# OnOnfre_Lights.net
KiCad netlist of a schematic drawn in EAGLE
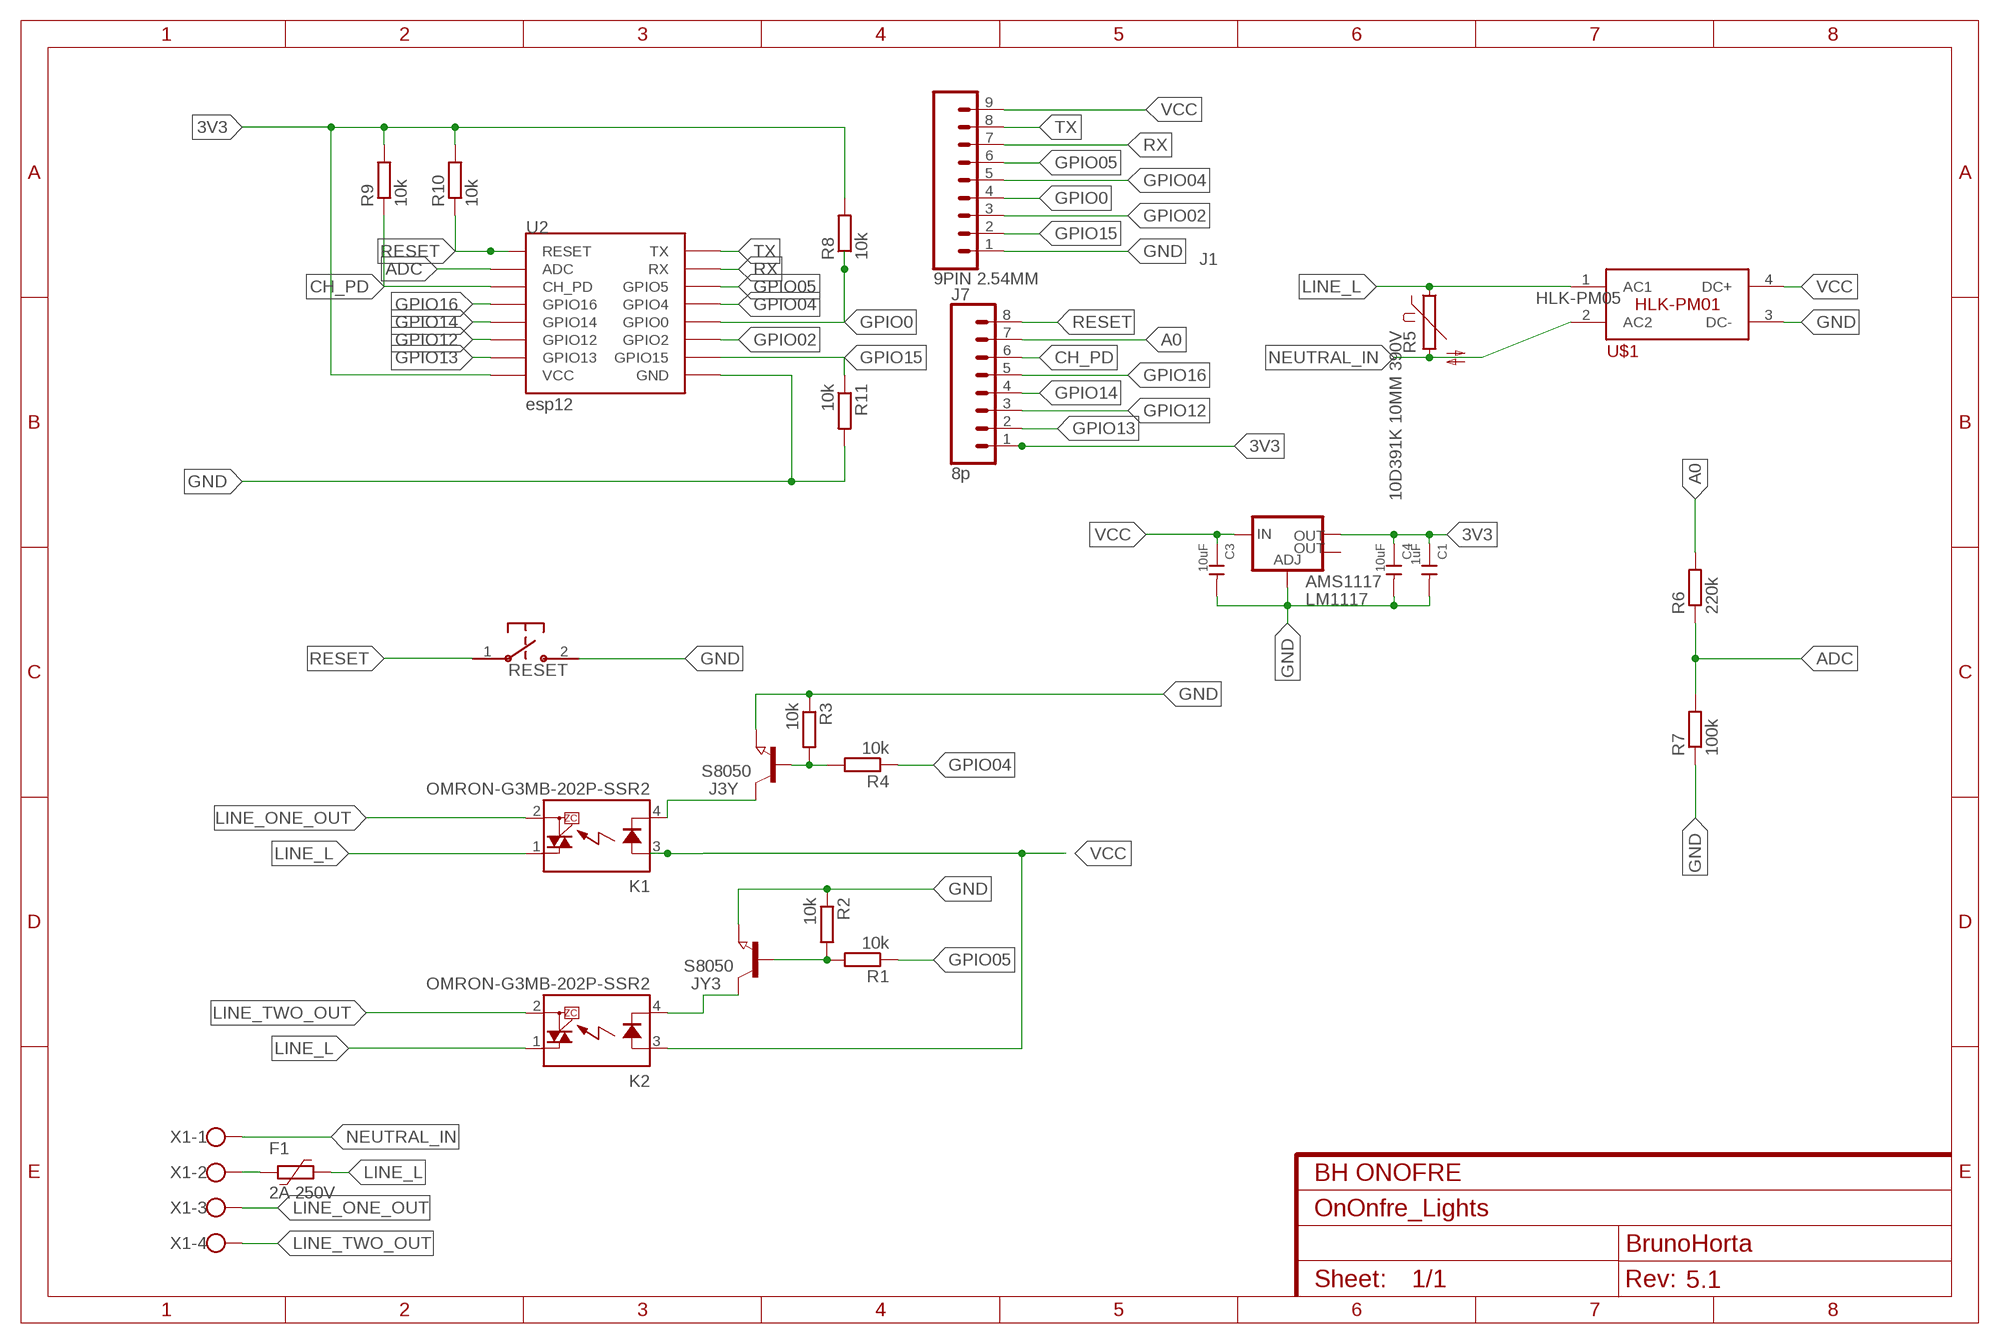
[diagram p0: schematic, sheet 1]

(export (version "E")
  (design (tool "Eeschema 10.0.6"))
  (components
    (comp (ref "AMS1117")
      (value "LM1117")
      (footprint "eagle-import:SOT223")
      (libsource (lib "eagle-import") (part "V_REG_LM1117SOT223"))
    )
    (comp (ref "C1")
      (value "1uF")
      (footprint "eagle-import:C1206")
      (fields (field (name "MPN") "CC1206KKX7RCBB102"))
      (libsource (lib "eagle-import") (part "CERAMIC-1NF-1KV-10%-X7R?(1206)"))
    )
    (comp (ref "C3")
      (value "10uF")
      (footprint "eagle-import:C1206")
      (fields (field (name "MPN") "CC1206KKX7RCBB102"))
      (libsource (lib "eagle-import") (part "CERAMIC-1NF-1KV-10%-X7R?(1206)"))
    )
    (comp (ref "C4")
      (value "10uF")
      (footprint "eagle-import:C1206")
      (fields (field (name "MPN") "CC1206KKX7RCBB102"))
      (libsource (lib "eagle-import") (part "CERAMIC-1NF-1KV-10%-X7R?(1206)"))
    )
    (comp (ref "F1")
      (value "2A 250V")
      (footprint "eagle-import:1812L")
      (fields (field (name "MF") "Littelfuse") (field (name "MPN") "1812L010"))
      (libsource (lib "eagle-import") (part "?1812L010"))
    )
    (comp (ref "J1")
      (value "9PIN 2.54MM")
      (footprint "eagle-import:1X09")
      (libsource (lib "eagle-import") (part "CONN_09"))
    )
    (comp (ref "J3Y")
      (value "S8050")
      (footprint "eagle-import:SOT23")
      (libsource (lib "eagle-import") (part "NPN-TRANSISTOR_SOT23"))
    )
    (comp (ref "J7")
      (value "8p")
      (footprint "eagle-import:1X08")
      (libsource (lib "eagle-import") (part "CONN_08{dblquote}"))
    )
    (comp (ref "JY3")
      (value "S8050")
      (footprint "eagle-import:SOT23")
      (libsource (lib "eagle-import") (part "NPN-TRANSISTOR_SOT23"))
    )
    (comp (ref "K1")
      (value "OMRON-G3MB-202P-SSR2")
      (footprint "eagle-import:OMRON-G3MB-202P-SSR")
      (fields (field (name "MPN") "S202S02F"))
      (libsource (lib "eagle-import") (part "OMRON-G3MB-202P-SSR2"))
    )
    (comp (ref "K2")
      (value "OMRON-G3MB-202P-SSR2")
      (footprint "eagle-import:OMRON-G3MB-202P-SSR")
      (fields (field (name "MPN") "S202S02F"))
      (libsource (lib "eagle-import") (part "OMRON-G3MB-202P-SSR2"))
    )
    (comp (ref "R1")
      (value "10k")
      (footprint "eagle-import:R0603")
      (libsource (lib "eagle-import") (part "R-EU_R0603"))
    )
    (comp (ref "R2")
      (value "10k")
      (footprint "eagle-import:R0603")
      (libsource (lib "eagle-import") (part "R-EU_R0603"))
    )
    (comp (ref "R3")
      (value "10k")
      (footprint "eagle-import:R0603")
      (libsource (lib "eagle-import") (part "R-EU_R0603"))
    )
    (comp (ref "R4")
      (value "10k")
      (footprint "eagle-import:R0603")
      (libsource (lib "eagle-import") (part "R-EU_R0603"))
    )
    (comp (ref "R5")
      (value "10D391K 10MM 390V")
      (footprint "eagle-import:S07K230")
      (libsource (lib "eagle-import") (part "S07K230"))
    )
    (comp (ref "R6")
      (value "220k")
      (footprint "eagle-import:R0603")
      (libsource (lib "eagle-import") (part "R-EU_R0603"))
    )
    (comp (ref "R7")
      (value "100k")
      (footprint "eagle-import:R0603")
      (libsource (lib "eagle-import") (part "R-EU_R0603"))
    )
    (comp (ref "R8")
      (value "10k")
      (footprint "eagle-import:R0603")
      (libsource (lib "eagle-import") (part "R-EU_R0603"))
    )
    (comp (ref "R9")
      (value "10k")
      (footprint "eagle-import:R0603")
      (libsource (lib "eagle-import") (part "R-EU_R0603"))
    )
    (comp (ref "R10")
      (value "10k")
      (footprint "eagle-import:R0603")
      (libsource (lib "eagle-import") (part "R-EU_R0603"))
    )
    (comp (ref "R11")
      (value "10k")
      (footprint "eagle-import:R0603")
      (libsource (lib "eagle-import") (part "R-EU_R0603"))
    )
    (comp (ref "RESET")
      (value "B3U-1000P-2P-SMD")
      (footprint "eagle-import:B3U-1000P")
      (fields (field (name "MANUFACTURER") "Omron") (field (name "MPN") "B3U-1000P"))
      (libsource (lib "eagle-import") (part "B3U-1000P"))
    )
    (comp (ref "U$1")
      (value "HLK-PM01")
      (footprint "eagle-import:HLK-PM01")
      (fields (field (name "MF") "Hi-link") (field (name "MP") "hlk-pm01"))
      (libsource (lib "eagle-import") (part "HLK-PM01"))
    )
    (comp (ref "U2")
      (value "esp12")
      (footprint "eagle-import:ESP12-SMD")
      (libsource (lib "eagle-import") (part "ESP12SMD"))
    )
    (comp (ref "X1")
      (value "W237-4")
      (footprint "eagle-import:W237-4")
      (libsource (lib "eagle-import") (part "W237-4"))
    )
  )
  (nets
    (net (code "1") (name "3V3") (class "Default")
      (node (ref "AMS1117") (pin "2") (pinfunction "OUT_2") (pintype "output"))
      (node (ref "C1") (pin "1") (pinfunction "1_1") (pintype "passive"))
      (node (ref "C4") (pin "1") (pinfunction "1_1") (pintype "passive"))
      (node (ref "J7") (pin "1") (pinfunction "1_1") (pintype "passive"))
      (node (ref "R10") (pin "2") (pinfunction "2_2") (pintype "passive"))
      (node (ref "R8") (pin "2") (pinfunction "2_2") (pintype "passive"))
      (node (ref "R9") (pin "2") (pinfunction "2_2") (pintype "passive"))
      (node (ref "U2") (pin "VCC") (pinfunction "VCC_VCC") (pintype "bidirectional"))
    )
    (net (code "2") (name "A0") (class "Default")
      (node (ref "J7") (pin "7") (pinfunction "7_7") (pintype "passive"))
      (node (ref "R6") (pin "2") (pinfunction "2_2") (pintype "passive"))
    )
    (net (code "3") (name "ADC") (class "Default")
      (node (ref "R6") (pin "1") (pinfunction "1_1") (pintype "passive"))
      (node (ref "R7") (pin "2") (pinfunction "2_2") (pintype "passive"))
      (node (ref "U2") (pin "ADC") (pinfunction "ADC_ADC") (pintype "bidirectional"))
    )
    (net (code "4") (name "CH_PD") (class "Default")
      (node (ref "J7") (pin "6") (pinfunction "6_6") (pintype "passive"))
      (node (ref "R9") (pin "1") (pinfunction "1_1") (pintype "passive"))
      (node (ref "U2") (pin "CH_PD") (pinfunction "CH_PD_CH_PD") (pintype "bidirectional"))
    )
    (net (code "5") (name "GND") (class "Default")
      (node (ref "AMS1117") (pin "1") (pinfunction "ADJ_1") (pintype "input"))
      (node (ref "C1") (pin "2") (pinfunction "2_2") (pintype "passive"))
      (node (ref "C3") (pin "2") (pinfunction "2_2") (pintype "passive"))
      (node (ref "C4") (pin "2") (pinfunction "2_2") (pintype "passive"))
      (node (ref "J1") (pin "1") (pinfunction "1_1") (pintype "passive"))
      (node (ref "J3Y") (pin "2") (pinfunction "E_2") (pintype "passive"))
      (node (ref "JY3") (pin "2") (pinfunction "E_2") (pintype "passive"))
      (node (ref "R11") (pin "2") (pinfunction "2_2") (pintype "passive"))
      (node (ref "R2") (pin "1") (pinfunction "1_1") (pintype "passive"))
      (node (ref "R3") (pin "1") (pinfunction "1_1") (pintype "passive"))
      (node (ref "R7") (pin "1") (pinfunction "1_1") (pintype "passive"))
      (node (ref "RESET") (pin "2") (pinfunction "P$2_2") (pintype "passive"))
      (node (ref "U$1") (pin "3") (pinfunction "DC-_3") (pintype "power_in"))
      (node (ref "U2") (pin "GND") (pinfunction "GND_GND") (pintype "bidirectional"))
    )
    (net (code "6") (name "GPIO0") (class "Default")
      (node (ref "J1") (pin "4") (pinfunction "4_4") (pintype "passive"))
      (node (ref "R8") (pin "1") (pinfunction "1_1") (pintype "passive"))
      (node (ref "U2") (pin "GPIO0") (pinfunction "GPIO0_GPIO0") (pintype "bidirectional"))
    )
    (net (code "7") (name "GPIO02") (class "Default")
      (node (ref "J1") (pin "3") (pinfunction "3_3") (pintype "passive"))
      (node (ref "U2") (pin "GPIO2") (pinfunction "GPIO2_GPIO2") (pintype "bidirectional"))
    )
    (net (code "8") (name "GPIO04") (class "Default")
      (node (ref "J1") (pin "5") (pinfunction "5_5") (pintype "passive"))
      (node (ref "R4") (pin "1") (pinfunction "1_1") (pintype "passive"))
      (node (ref "U2") (pin "GPIO4") (pinfunction "GPIO4_GPIO4") (pintype "bidirectional"))
    )
    (net (code "9") (name "GPIO05") (class "Default")
      (node (ref "J1") (pin "6") (pinfunction "6_6") (pintype "passive"))
      (node (ref "R1") (pin "1") (pinfunction "1_1") (pintype "passive"))
      (node (ref "U2") (pin "GPIO5") (pinfunction "GPIO5_GPIO5") (pintype "bidirectional"))
    )
    (net (code "10") (name "GPIO12") (class "Default")
      (node (ref "J7") (pin "3") (pinfunction "3_3") (pintype "passive"))
      (node (ref "U2") (pin "GPIO12") (pinfunction "GPIO12_GPIO12") (pintype "bidirectional"))
    )
    (net (code "11") (name "GPIO13") (class "Default")
      (node (ref "J7") (pin "2") (pinfunction "2_2") (pintype "passive"))
      (node (ref "U2") (pin "GPIO13") (pinfunction "GPIO13_GPIO13") (pintype "bidirectional"))
    )
    (net (code "12") (name "GPIO14") (class "Default")
      (node (ref "J7") (pin "4") (pinfunction "4_4") (pintype "passive"))
      (node (ref "U2") (pin "GPIO14") (pinfunction "GPIO14_GPIO14") (pintype "bidirectional"))
    )
    (net (code "13") (name "GPIO15") (class "Default")
      (node (ref "J1") (pin "2") (pinfunction "2_2") (pintype "passive"))
      (node (ref "R11") (pin "1") (pinfunction "1_1") (pintype "passive"))
      (node (ref "U2") (pin "GPIO15") (pinfunction "GPIO15_GPIO15") (pintype "bidirectional"))
    )
    (net (code "14") (name "GPIO16") (class "Default")
      (node (ref "J7") (pin "5") (pinfunction "5_5") (pintype "passive"))
      (node (ref "U2") (pin "GPIO16") (pinfunction "GPIO16_GPIO16") (pintype "bidirectional"))
    )
    (net (code "15") (name "LINE_L") (class "Default")
      (node (ref "F1") (pin "1") (pinfunction "1_1") (pintype "passive"))
      (node (ref "K1") (pin "1") (pinfunction "DS1_1") (pintype "passive"))
      (node (ref "K2") (pin "1") (pinfunction "DS1_1") (pintype "passive"))
      (node (ref "R5") (pin "1") (pinfunction "1_1") (pintype "passive"))
      (node (ref "U$1") (pin "1") (pinfunction "AC1_1") (pintype "power_in"))
    )
    (net (code "16") (name "LINE_ONE_OUT") (class "Default")
      (node (ref "K1") (pin "2") (pinfunction "DS2_2") (pintype "passive"))
      (node (ref "X1") (pin "3") (pinfunction "KL_3") (pintype "passive"))
    )
    (net (code "17") (name "LINE_TWO_OUT") (class "Default")
      (node (ref "K2") (pin "2") (pinfunction "DS2_2") (pintype "passive"))
      (node (ref "X1") (pin "4") (pinfunction "KL_4") (pintype "passive"))
    )
    (net (code "18") (name "NEUTRAL_IN") (class "Default")
      (node (ref "R5") (pin "2") (pinfunction "2_2") (pintype "passive"))
      (node (ref "U$1") (pin "2") (pinfunction "AC2_2") (pintype "power_in"))
      (node (ref "X1") (pin "1") (pinfunction "KL_1") (pintype "passive"))
    )
    (net (code "19") (name "Net-(J3Y-B)") (class "Default")
      (node (ref "J3Y") (pin "1") (pinfunction "B_1") (pintype "passive"))
      (node (ref "R3") (pin "2") (pinfunction "2_2") (pintype "passive"))
      (node (ref "R4") (pin "2") (pinfunction "2_2") (pintype "passive"))
    )
    (net (code "20") (name "Net-(J3Y-C)") (class "Default")
      (node (ref "J3Y") (pin "3") (pinfunction "C_3") (pintype "passive"))
      (node (ref "K1") (pin "4") (pinfunction "K_4") (pintype "passive"))
    )
    (net (code "21") (name "Net-(JY3-B)") (class "Default")
      (node (ref "JY3") (pin "1") (pinfunction "B_1") (pintype "passive"))
      (node (ref "R1") (pin "2") (pinfunction "2_2") (pintype "passive"))
      (node (ref "R2") (pin "2") (pinfunction "2_2") (pintype "passive"))
    )
    (net (code "22") (name "Net-(JY3-C)") (class "Default")
      (node (ref "JY3") (pin "3") (pinfunction "C_3") (pintype "passive"))
      (node (ref "K2") (pin "4") (pinfunction "K_4") (pintype "passive"))
    )
    (net (code "23") (name "Net-(X1B-KL)") (class "Default")
      (node (ref "F1") (pin "2") (pinfunction "2_2") (pintype "passive"))
      (node (ref "X1") (pin "2") (pinfunction "KL_2") (pintype "passive"))
    )
    (net (code "24") (name "RESET") (class "Default")
      (node (ref "J7") (pin "8") (pinfunction "8_8") (pintype "passive"))
      (node (ref "R10") (pin "1") (pinfunction "1_1") (pintype "passive"))
      (node (ref "RESET") (pin "1") (pinfunction "P$1_1") (pintype "passive"))
      (node (ref "U2") (pin "RESET") (pinfunction "RESET_RESET") (pintype "bidirectional"))
    )
    (net (code "25") (name "RX") (class "Default")
      (node (ref "J1") (pin "7") (pinfunction "7_7") (pintype "passive"))
      (node (ref "U2") (pin "RXD0") (pinfunction "RX_RXD0") (pintype "bidirectional"))
    )
    (net (code "26") (name "TX") (class "Default")
      (node (ref "J1") (pin "8") (pinfunction "8_8") (pintype "passive"))
      (node (ref "U2") (pin "TXD0") (pinfunction "TX_TXD0") (pintype "bidirectional"))
    )
    (net (code "27") (name "VCC") (class "Default")
      (node (ref "AMS1117") (pin "3") (pinfunction "IN_3") (pintype "input"))
      (node (ref "C3") (pin "1") (pinfunction "1_1") (pintype "passive"))
      (node (ref "J1") (pin "9") (pinfunction "9_9") (pintype "passive"))
      (node (ref "K1") (pin "3") (pinfunction "A_3") (pintype "passive"))
      (node (ref "K2") (pin "3") (pinfunction "A_3") (pintype "passive"))
      (node (ref "U$1") (pin "4") (pinfunction "DC+_4") (pintype "power_in"))
    )
    (net (code "28") (name "unconnected-(AMS1117-OUT-Pad4)") (class "Default")
      (node (ref "AMS1117") (pin "4") (pinfunction "OUT_4") (pintype "output"))
    )
  )
)
